# Power.net
KiCad netlist of a schematic drawn in Altium Designer
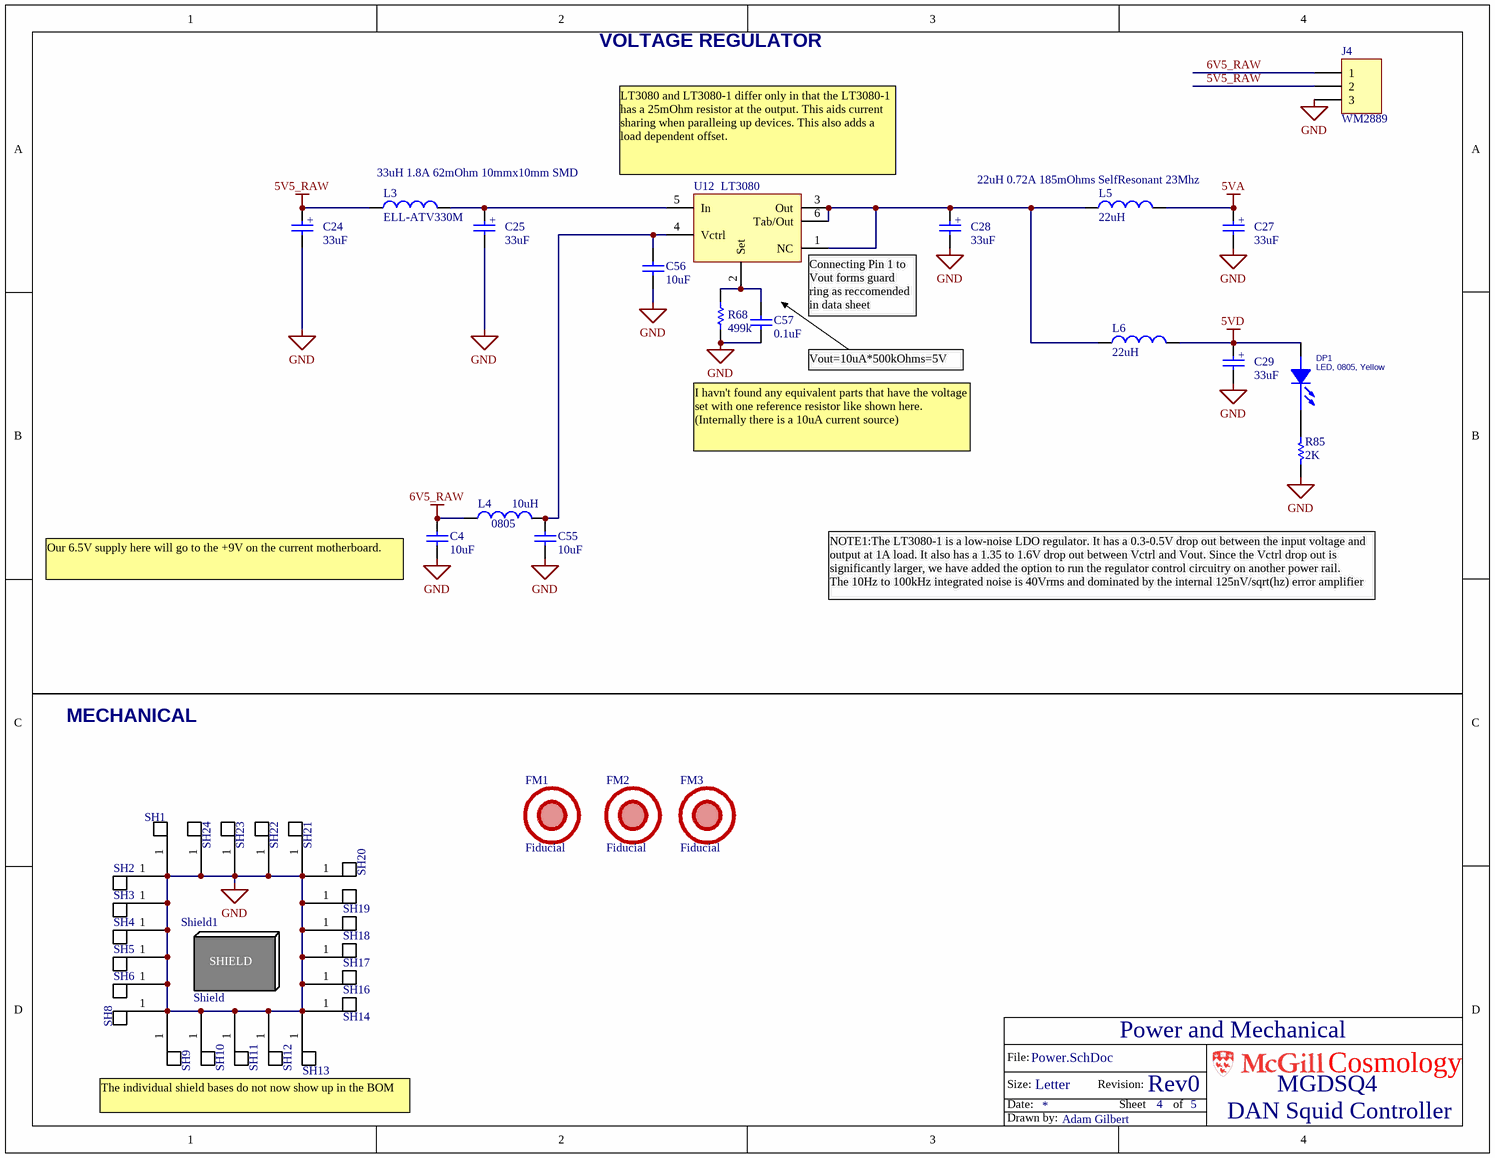
[diagram p0: Power.SchDoc]

(export (version "E")
  (design (tool "Eeschema 10.0.6"))
  (components
    (comp (ref "C4")
      (value "10uF")
      (footprint "0603")
      (description "Capacitor, Ceramic, 0603")
      (fields (field (name "MANUFACTURER") "Generic"))
      (libsource (lib "MiniSquidCtrl") (part "Cap0603"))
    )
    (comp (ref "C24")
      (value "33uF")
      (footprint "TCASE-D")
      (description "CAP TANT CASE-D")
      (fields (field (name "VOLTAGE") "16V") (field (name "MANUFACTURER") "Generic"))
      (libsource (lib "MiniSquidCtrl") (part "Tantalum"))
    )
    (comp (ref "C25")
      (value "33uF")
      (footprint "TCASE-D")
      (description "CAP TANT CASE-D")
      (fields (field (name "VOLTAGE") "16V") (field (name "MANUFACTURER") "Generic"))
      (libsource (lib "MiniSquidCtrl") (part "Tantalum"))
    )
    (comp (ref "C27")
      (value "33uF")
      (footprint "TCASE-D")
      (description "CAP TANT CASE-D")
      (fields (field (name "VOLTAGE") "16V") (field (name "MANUFACTURER") "Generic"))
      (libsource (lib "MiniSquidCtrl") (part "Tantalum"))
    )
    (comp (ref "C28")
      (value "33uF")
      (footprint "TCASE-D")
      (description "CAP TANT CASE-D")
      (fields (field (name "VOLTAGE") "16V") (field (name "MANUFACTURER") "Generic"))
      (libsource (lib "MiniSquidCtrl") (part "Tantalum"))
    )
    (comp (ref "C29")
      (value "33uF")
      (footprint "TCASE-D")
      (description "CAP TANT CASE-D")
      (fields (field (name "VOLTAGE") "16V") (field (name "MANUFACTURER") "Generic"))
      (libsource (lib "MiniSquidCtrl") (part "Tantalum"))
    )
    (comp (ref "C55")
      (value "10uF")
      (footprint "0603")
      (description "Capacitor, Ceramic, 0603")
      (fields (field (name "MANUFACTURER") "Generic"))
      (libsource (lib "MiniSquidCtrl") (part "Cap0603"))
    )
    (comp (ref "C56")
      (value "10uF")
      (footprint "0603")
      (description "Capacitor, Ceramic, 0603")
      (fields (field (name "MANUFACTURER") "Generic"))
      (libsource (lib "MiniSquidCtrl") (part "Cap0603"))
    )
    (comp (ref "C57")
      (value "0.1uF")
      (footprint "0603")
      (description "Capacitor, Ceramic, 0603")
      (fields (field (name "MANUFACTURER") "Generic"))
      (libsource (lib "MiniSquidCtrl") (part "Cap0603"))
    )
    (comp (ref "DP1")
      (value "LED, 0805, Yellow")
      (description "LED")
      (libsource (lib "MiniSquidCtrl") (part "LED, yellow, 0805, 2mA"))
    )
    (comp (ref "FM1")
      (value "Fiducial")
      (footprint "Fiducial_mark")
      (libsource (lib "MiniSquidCtrl") (part "Fiducial"))
    )
    (comp (ref "FM2")
      (value "Fiducial")
      (footprint "Fiducial_mark")
      (libsource (lib "MiniSquidCtrl") (part "Fiducial"))
    )
    (comp (ref "FM3")
      (value "Fiducial")
      (footprint "Fiducial_mark")
      (libsource (lib "MiniSquidCtrl") (part "Fiducial"))
    )
    (comp (ref "J4")
      (value "WM2889")
      (footprint "HDR1X3_MolexVertical")
      (description "3-Pin 0.1\" header")
      (fields (field (name "MANUFACTURER") "Digikey"))
      (libsource (lib "MiniSquidCtrl") (part "Header 3"))
    )
    (comp (ref "L3")
      (value "ELL-ATV330M")
      (footprint "ELLATV")
      (description "33uH 1.8A 62mOhm 10mmx10mm SMD")
      (fields (field (name "MANUFACTURER") "Panasonic - ECG") (field (name "TOLERANCE") "±20%"))
      (libsource (lib "MiniSquidCtrl") (part "ELL-ATV330M"))
    )
    (comp (ref "L4")
      (value "10uH")
      (footprint "0805")
      (description "Inductor 0805")
      (fields (field (name "MANUFACTURER") "TDK Corporation"))
      (libsource (lib "MiniSquidCtrl") (part "Inductor0603"))
    )
    (comp (ref "L5")
      (value "22uH")
      (footprint "SRR4028")
      (description "=PartConstraints")
      (fields
        (field (name "MANUFACTURER") "Bourns")
        (field (name "PARTCONSTRAINTS") "22uH 0.72A 185mOhms SelfResonant 23Mhz")
      )
      (libsource (lib "MiniSquidCtrl") (part "InductorSRR4028"))
    )
    (comp (ref "L6")
      (value "22uH")
      (footprint "SRR4028")
      (description "=PartConstraints")
      (fields (field (name "MANUFACTURER") "Bourns"))
      (libsource (lib "MiniSquidCtrl") (part "InductorSRR4028"))
    )
    (comp (ref "R68")
      (value "499k")
      (footprint "0603")
      (description "RES 0603")
      (fields (field (name "MANUFACTURER") "Generic"))
      (libsource (lib "MiniSquidCtrl") (part "RES 0603"))
    )
    (comp (ref "R85")
      (value "2K")
      (footprint "0603")
      (description "RES 0603")
      (fields (field (name "MANUFACTURER") "Generic") (field (name "Comment") "2k"))
      (libsource (lib "MiniSquidCtrl") (part "Res0603"))
    )
    (comp (ref "SH1")
      (value "LeaderTech 20S-CBS-2x0.5x0.2 - DIVIDE QUANITY REQURIED BY 10!")
      (footprint "SHIELD BASE CORNER")
      (fields (field (name "MANUFACTURER") "LeaderTech"))
      (libsource (lib "MiniSquidCtrl") (part "ShieldBase"))
    )
    (comp (ref "SH2")
      (value "LeaderTech 20S-CBS-2x0.5x0.2 - DIVIDE QUANITY REQURIED BY 10!")
      (footprint "SHIELD BASE")
      (fields (field (name "MANUFACTURER") "LeaderTech"))
      (libsource (lib "MiniSquidCtrl") (part "ShieldBase"))
    )
    (comp (ref "SH3")
      (value "LeaderTech 20S-CBS-2x0.5x0.2 - DIVIDE QUANITY REQURIED BY 10!")
      (footprint "SHIELD BASE")
      (fields (field (name "MANUFACTURER") "LeaderTech"))
      (libsource (lib "MiniSquidCtrl") (part "ShieldBase"))
    )
    (comp (ref "SH4")
      (value "LeaderTech 20S-CBS-2x0.5x0.2 - DIVIDE QUANITY REQURIED BY 10!")
      (footprint "SHIELD BASE")
      (fields (field (name "MANUFACTURER") "LeaderTech"))
      (libsource (lib "MiniSquidCtrl") (part "ShieldBase"))
    )
    (comp (ref "SH5")
      (value "LeaderTech 20S-CBS-2x0.5x0.2 - DIVIDE QUANITY REQURIED BY 10!")
      (footprint "SHIELD BASE")
      (fields (field (name "MANUFACTURER") "LeaderTech"))
      (libsource (lib "MiniSquidCtrl") (part "ShieldBase"))
    )
    (comp (ref "SH6")
      (value "LeaderTech 20S-CBS-2x0.5x0.2 - DIVIDE QUANITY REQURIED BY 10!")
      (footprint "SHIELD BASE")
      (fields (field (name "MANUFACTURER") "LeaderTech"))
      (libsource (lib "MiniSquidCtrl") (part "ShieldBase"))
    )
    (comp (ref "SH8")
      (value "LeaderTech 20S-CBS-2x0.5x0.2 - DIVIDE QUANITY REQURIED BY 10!")
      (footprint "SHIELD BASE CORNER")
      (fields (field (name "MANUFACTURER") "LeaderTech"))
      (libsource (lib "MiniSquidCtrl") (part "ShieldBase"))
    )
    (comp (ref "SH9")
      (value "LeaderTech 20S-CBS-2x0.5x0.2 - DIVIDE QUANITY REQURIED BY 10!")
      (footprint "SHIELD BASE")
      (fields (field (name "MANUFACTURER") "LeaderTech"))
      (libsource (lib "MiniSquidCtrl") (part "ShieldBase"))
    )
    (comp (ref "SH10")
      (value "LeaderTech 20S-CBS-2x0.5x0.2 - DIVIDE QUANITY REQURIED BY 10!")
      (footprint "SHIELD BASE")
      (fields (field (name "MANUFACTURER") "LeaderTech"))
      (libsource (lib "MiniSquidCtrl") (part "ShieldBase"))
    )
    (comp (ref "SH11")
      (value "LeaderTech 20S-CBS-2x0.5x0.2 - DIVIDE QUANITY REQURIED BY 10!")
      (footprint "SHIELD BASE")
      (fields (field (name "MANUFACTURER") "LeaderTech"))
      (libsource (lib "MiniSquidCtrl") (part "ShieldBase"))
    )
    (comp (ref "SH12")
      (value "LeaderTech 20S-CBS-2x0.5x0.2 - DIVIDE QUANITY REQURIED BY 10!")
      (footprint "SHIELD BASE")
      (fields (field (name "MANUFACTURER") "LeaderTech"))
      (libsource (lib "MiniSquidCtrl") (part "ShieldBase"))
    )
    (comp (ref "SH13")
      (value "LeaderTech 20S-CBS-2x0.5x0.2 - DIVIDE QUANITY REQURIED BY 10!")
      (footprint "SHIELD BASE CORNER")
      (fields (field (name "MANUFACTURER") "LeaderTech"))
      (libsource (lib "MiniSquidCtrl") (part "ShieldBase"))
    )
    (comp (ref "SH14")
      (value "LeaderTech 20S-CBS-2x0.5x0.2 - DIVIDE QUANITY REQURIED BY 10!")
      (footprint "SHIELD BASE")
      (fields (field (name "MANUFACTURER") "LeaderTech"))
      (libsource (lib "MiniSquidCtrl") (part "ShieldBase"))
    )
    (comp (ref "SH16")
      (value "LeaderTech 20S-CBS-2x0.5x0.2 - DIVIDE QUANITY REQURIED BY 10!")
      (footprint "SHIELD BASE")
      (fields (field (name "MANUFACTURER") "LeaderTech"))
      (libsource (lib "MiniSquidCtrl") (part "ShieldBase"))
    )
    (comp (ref "SH17")
      (value "LeaderTech 20S-CBS-2x0.5x0.2 - DIVIDE QUANITY REQURIED BY 10!")
      (footprint "SHIELD BASE")
      (fields (field (name "MANUFACTURER") "LeaderTech"))
      (libsource (lib "MiniSquidCtrl") (part "ShieldBase"))
    )
    (comp (ref "SH18")
      (value "LeaderTech 20S-CBS-2x0.5x0.2 - DIVIDE QUANITY REQURIED BY 10!")
      (footprint "SHIELD BASE")
      (fields (field (name "MANUFACTURER") "LeaderTech"))
      (libsource (lib "MiniSquidCtrl") (part "ShieldBase"))
    )
    (comp (ref "SH19")
      (value "LeaderTech 20S-CBS-2x0.5x0.2 - DIVIDE QUANITY REQURIED BY 10!")
      (footprint "SHIELD BASE")
      (fields (field (name "MANUFACTURER") "LeaderTech"))
      (libsource (lib "MiniSquidCtrl") (part "ShieldBase"))
    )
    (comp (ref "SH20")
      (value "LeaderTech 20S-CBS-2x0.5x0.2 - DIVIDE QUANITY REQURIED BY 10!")
      (footprint "SHIELD BASE CORNER")
      (fields (field (name "MANUFACTURER") "LeaderTech"))
      (libsource (lib "MiniSquidCtrl") (part "ShieldBase"))
    )
    (comp (ref "SH21")
      (value "LeaderTech 20S-CBS-2x0.5x0.2 - DIVIDE QUANITY REQURIED BY 10!")
      (footprint "SHIELD BASE")
      (fields (field (name "MANUFACTURER") "LeaderTech"))
      (libsource (lib "MiniSquidCtrl") (part "ShieldBase"))
    )
    (comp (ref "SH22")
      (value "LeaderTech 20S-CBS-2x0.5x0.2 - DIVIDE QUANITY REQURIED BY 10!")
      (footprint "SHIELD BASE")
      (fields (field (name "MANUFACTURER") "LeaderTech"))
      (libsource (lib "MiniSquidCtrl") (part "ShieldBase"))
    )
    (comp (ref "SH23")
      (value "LeaderTech 20S-CBS-2x0.5x0.2 - DIVIDE QUANITY REQURIED BY 10!")
      (footprint "SHIELD BASE")
      (fields (field (name "MANUFACTURER") "LeaderTech"))
      (libsource (lib "MiniSquidCtrl") (part "ShieldBase"))
    )
    (comp (ref "SH24")
      (value "LeaderTech 20S-CBS-2x0.5x0.2 - DIVIDE QUANITY REQURIED BY 10!")
      (footprint "SHIELD BASE")
      (fields (field (name "MANUFACTURER") "LeaderTech"))
      (libsource (lib "MiniSquidCtrl") (part "ShieldBase"))
    )
    (comp (ref "Shield1")
      (value "Shield")
      (description "20S-CBSA-3x2.5x0.2 (assembled fence and cover)")
      (fields (field (name "MANUFACTURER") "Leadertech"))
      (libsource (lib "MiniSquidCtrl") (part "SHIELD 20S-CBS-3x2.5x0.2"))
    )
    (comp (ref "U12")
      (value "LT3080")
      (footprint "D2-PAK-6_LT3080")
      (description "Low dropout regulator, single resistor, 1.1A")
      (fields (field (name "MANUFACTURER") "Linear Technology"))
      (libsource (lib "MiniSquidCtrl") (part "LT3080"))
    )
  )
  (nets
    (net (code "1") (name "5V5_RAW") (class "Default")
      (node (ref "C24") (pin "1") (pinfunction "1_1") (pintype "passive"))
      (node (ref "J4") (pin "2") (pinfunction "2_2") (pintype "passive"))
      (node (ref "L3") (pin "1") (pinfunction "1_1") (pintype "passive"))
    )
    (net (code "2") (name "5VA") (class "Default")
      (node (ref "C27") (pin "1") (pinfunction "1_1") (pintype "passive"))
      (node (ref "L5") (pin "2") (pinfunction "2_2") (pintype "passive"))
    )
    (net (code "3") (name "5VD") (class "Default")
      (node (ref "C29") (pin "1") (pinfunction "1_1") (pintype "passive"))
      (node (ref "DP1") (pin "1") (pinfunction "ANODE_1") (pintype "passive"))
      (node (ref "L6") (pin "2") (pinfunction "2_2") (pintype "passive"))
    )
    (net (code "4") (name "6V5_RAW") (class "Default")
      (node (ref "C4") (pin "2") (pinfunction "2_2") (pintype "passive"))
      (node (ref "J4") (pin "1") (pinfunction "1_1") (pintype "passive"))
      (node (ref "L4") (pin "2") (pinfunction "2_2") (pintype "passive"))
    )
    (net (code "5") (name "GND") (class "Default")
      (node (ref "C24") (pin "2") (pinfunction "2_2") (pintype "passive"))
      (node (ref "C25") (pin "2") (pinfunction "2_2") (pintype "passive"))
      (node (ref "C27") (pin "2") (pinfunction "2_2") (pintype "passive"))
      (node (ref "C28") (pin "2") (pinfunction "2_2") (pintype "passive"))
      (node (ref "C29") (pin "2") (pinfunction "2_2") (pintype "passive"))
      (node (ref "C4") (pin "1") (pinfunction "1_1") (pintype "passive"))
      (node (ref "C55") (pin "1") (pinfunction "1_1") (pintype "passive"))
      (node (ref "C56") (pin "1") (pinfunction "1_1") (pintype "passive"))
      (node (ref "C57") (pin "1") (pinfunction "1_1") (pintype "passive"))
      (node (ref "J4") (pin "3") (pinfunction "3_3") (pintype "passive"))
      (node (ref "R68") (pin "1") (pinfunction "1_1") (pintype "passive"))
      (node (ref "R85") (pin "2") (pinfunction "2_2") (pintype "passive"))
      (node (ref "SH1") (pin "1") (pinfunction "1_1") (pintype "passive"))
      (node (ref "SH10") (pin "1") (pinfunction "1_1") (pintype "passive"))
      (node (ref "SH11") (pin "1") (pinfunction "1_1") (pintype "passive"))
      (node (ref "SH12") (pin "1") (pinfunction "1_1") (pintype "passive"))
      (node (ref "SH13") (pin "1") (pinfunction "1_1") (pintype "passive"))
      (node (ref "SH14") (pin "1") (pinfunction "1_1") (pintype "passive"))
      (node (ref "SH16") (pin "1") (pinfunction "1_1") (pintype "passive"))
      (node (ref "SH17") (pin "1") (pinfunction "1_1") (pintype "passive"))
      (node (ref "SH18") (pin "1") (pinfunction "1_1") (pintype "passive"))
      (node (ref "SH19") (pin "1") (pinfunction "1_1") (pintype "passive"))
      (node (ref "SH2") (pin "1") (pinfunction "1_1") (pintype "passive"))
      (node (ref "SH20") (pin "1") (pinfunction "1_1") (pintype "passive"))
      (node (ref "SH21") (pin "1") (pinfunction "1_1") (pintype "passive"))
      (node (ref "SH22") (pin "1") (pinfunction "1_1") (pintype "passive"))
      (node (ref "SH23") (pin "1") (pinfunction "1_1") (pintype "passive"))
      (node (ref "SH24") (pin "1") (pinfunction "1_1") (pintype "passive"))
      (node (ref "SH3") (pin "1") (pinfunction "1_1") (pintype "passive"))
      (node (ref "SH4") (pin "1") (pinfunction "1_1") (pintype "passive"))
      (node (ref "SH5") (pin "1") (pinfunction "1_1") (pintype "passive"))
      (node (ref "SH6") (pin "1") (pinfunction "1_1") (pintype "passive"))
      (node (ref "SH8") (pin "1") (pinfunction "1_1") (pintype "passive"))
      (node (ref "SH9") (pin "1") (pinfunction "1_1") (pintype "passive"))
    )
    (net (code "6") (name "Net-(DP1-CATHODE)") (class "Default")
      (node (ref "DP1") (pin "2") (pinfunction "CATHODE_2") (pintype "passive"))
      (node (ref "R85") (pin "1") (pinfunction "1_1") (pintype "passive"))
    )
    (net (code "7") (name "Net-(U12-In)") (class "Default")
      (node (ref "C25") (pin "1") (pinfunction "1_1") (pintype "passive"))
      (node (ref "L3") (pin "2") (pinfunction "2_2") (pintype "passive"))
      (node (ref "U12") (pin "5") (pinfunction "In_5") (pintype "power_in"))
    )
    (net (code "8") (name "Net-(U12-NC)") (class "Default")
      (node (ref "C28") (pin "1") (pinfunction "1_1") (pintype "passive"))
      (node (ref "L5") (pin "1") (pinfunction "1_1") (pintype "passive"))
      (node (ref "L6") (pin "1") (pinfunction "1_1") (pintype "passive"))
      (node (ref "U12") (pin "1") (pinfunction "NC_1") (pintype "power_in"))
      (node (ref "U12") (pin "3") (pinfunction "Out_3") (pintype "power_in"))
      (node (ref "U12") (pin "6") (pinfunction "Tab/Out_6") (pintype "power_in"))
    )
    (net (code "9") (name "Net-(U12-Set)") (class "Default")
      (node (ref "C57") (pin "2") (pinfunction "2_2") (pintype "passive"))
      (node (ref "R68") (pin "2") (pinfunction "2_2") (pintype "passive"))
      (node (ref "U12") (pin "2") (pinfunction "Set_2") (pintype "power_in"))
    )
    (net (code "10") (name "Net-(U12-Vctrl)") (class "Default")
      (node (ref "C55") (pin "2") (pinfunction "2_2") (pintype "passive"))
      (node (ref "C56") (pin "2") (pinfunction "2_2") (pintype "passive"))
      (node (ref "L4") (pin "1") (pinfunction "1_1") (pintype "passive"))
      (node (ref "U12") (pin "4") (pinfunction "Vctrl_4") (pintype "power_in"))
    )
  )
)
